# sequint.net
KiCad netlist of a schematic drawn in EAGLE
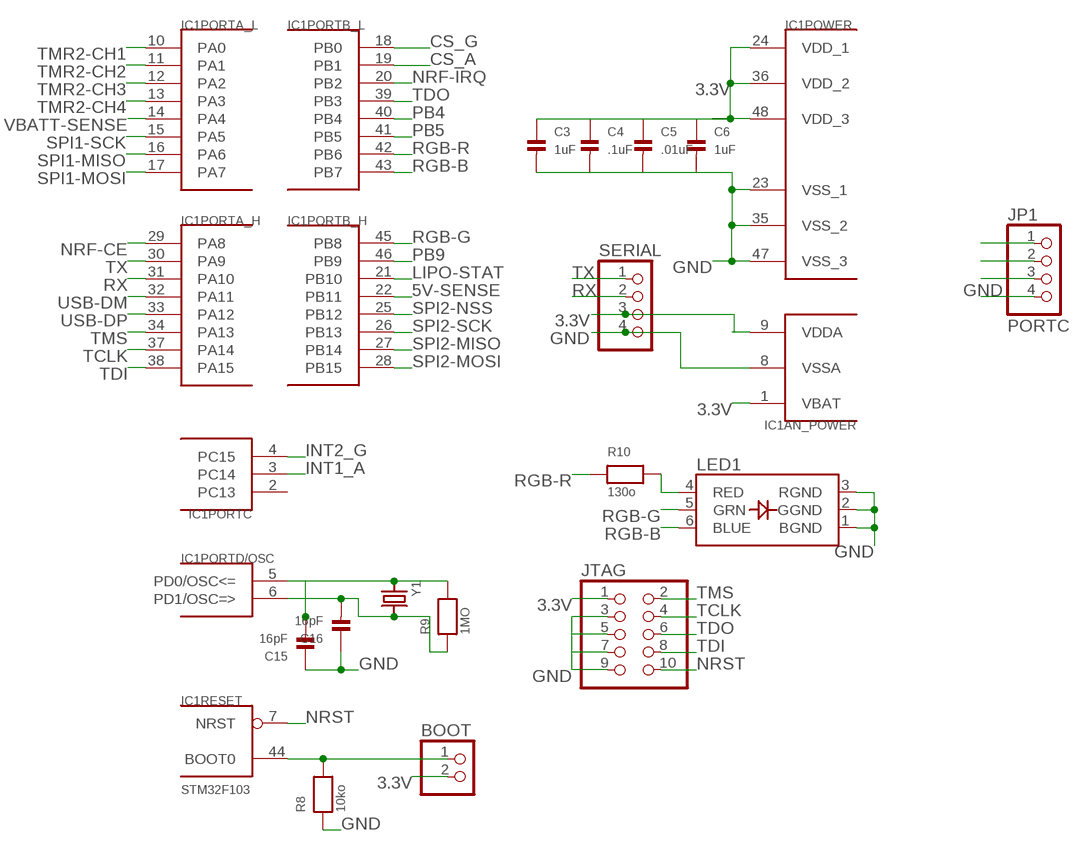
[diagram p0: schematic, sheet 1]
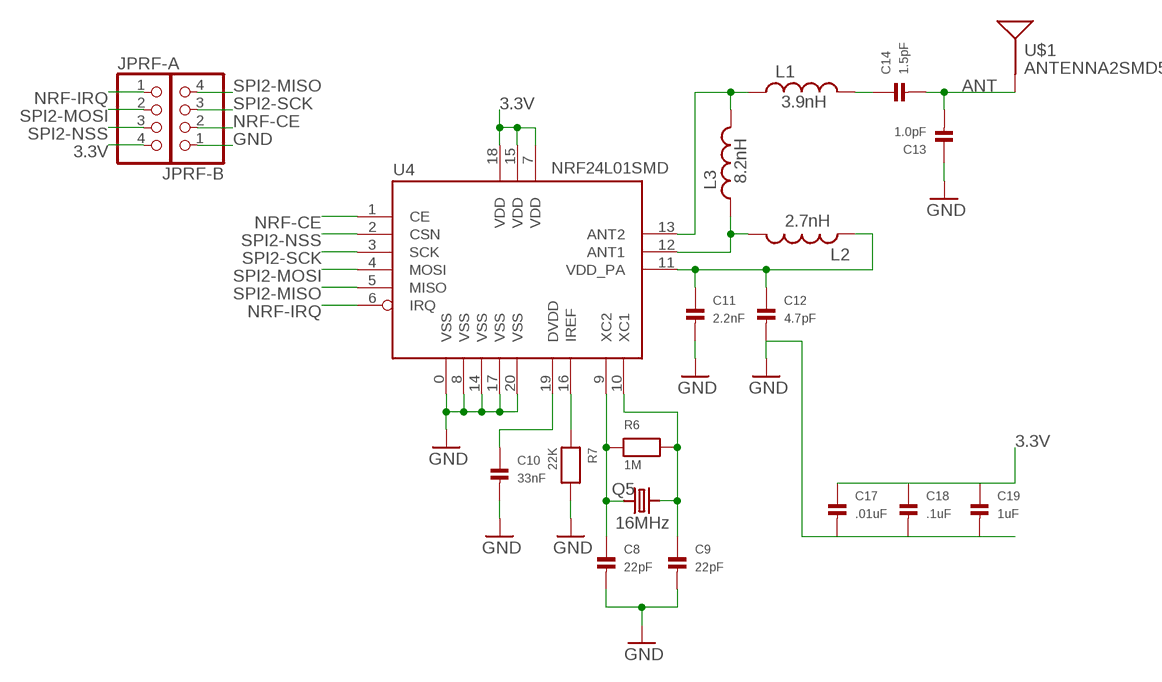
[diagram p1: schematic, sheet 2]
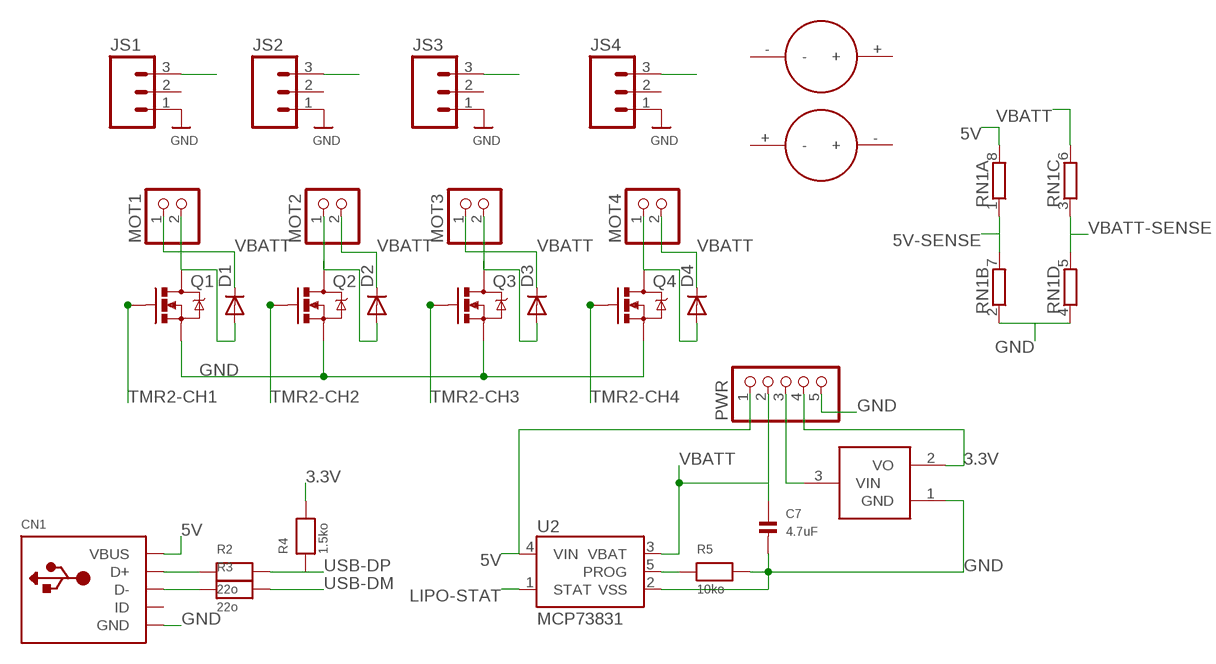
[diagram p2: schematic, sheet 3]
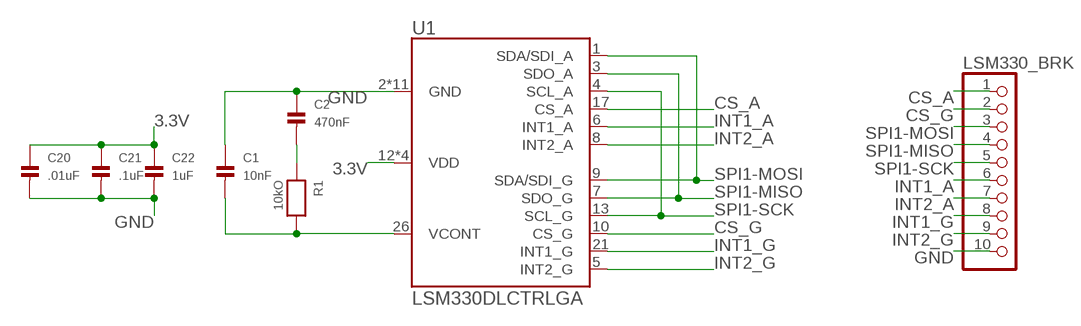
[diagram p3: schematic, sheet 4]

(export (version "E")
  (design (tool "Eeschema 10.0.6"))
  (components
    (comp (ref "C1")
      (value "10nF")
      (footprint "eagle-import:0402")
      (libsource (lib "eagle-import") (part "CAP_CERAMIC0402"))
    )
    (comp (ref "C2")
      (value "470nF")
      (footprint "eagle-import:0402")
      (libsource (lib "eagle-import") (part "CAP_CERAMIC0402"))
    )
    (comp (ref "C20")
      (value ".01uF")
      (footprint "eagle-import:0402")
      (libsource (lib "eagle-import") (part "CAP_CERAMIC0402"))
    )
    (comp (ref "C21")
      (value ".1uF")
      (footprint "eagle-import:0402")
      (libsource (lib "eagle-import") (part "CAP_CERAMIC0402"))
    )
    (comp (ref "C22")
      (value "1uF")
      (footprint "eagle-import:0402")
      (libsource (lib "eagle-import") (part "CAP_CERAMIC0402"))
    )
    (comp (ref "LSM330_BRK")
      (value "HEADER-1X10ROUND")
      (footprint "eagle-import:1X10_ROUND")
      (libsource (lib "eagle-import") (part "HEADER-1X10ROUND"))
    )
    (comp (ref "R1")
      (value "10kO")
      (footprint "eagle-import:0402")
      (libsource (lib "eagle-import") (part "RESISTOR0402"))
    )
    (comp (ref "U1")
      (value "LSM330DLCTRLGA")
      (footprint "eagle-import:LGA28L")
      (libsource (lib "eagle-import") (part "LSM330DLCTRLGA"))
    )
    (comp (ref "BOOT")
      (value "HEADER-1X2ROUND")
      (footprint "eagle-import:1X02_ROUND")
      (libsource (lib "eagle-import") (part "HEADER-1X2ROUND"))
    )
    (comp (ref "C3")
      (value "1uF")
      (footprint "eagle-import:0402")
      (libsource (lib "eagle-import") (part "CAP_CERAMIC0402"))
    )
    (comp (ref "C4")
      (value ".1uF")
      (footprint "eagle-import:0402")
      (libsource (lib "eagle-import") (part "CAP_CERAMIC0402"))
    )
    (comp (ref "C5")
      (value ".01uF")
      (footprint "eagle-import:0402")
      (libsource (lib "eagle-import") (part "CAP_CERAMIC0402"))
    )
    (comp (ref "C6")
      (value "1uF")
      (footprint "eagle-import:0402")
      (libsource (lib "eagle-import") (part "CAP_CERAMIC0402"))
    )
    (comp (ref "C15")
      (value "16pF")
      (footprint "eagle-import:0402")
      (libsource (lib "eagle-import") (part "CAP_CERAMIC0402"))
    )
    (comp (ref "C16")
      (value "16pF")
      (footprint "eagle-import:0402")
      (libsource (lib "eagle-import") (part "CAP_CERAMIC0402"))
    )
    (comp (ref "IC1")
      (value "STM32F103")
      (footprint "eagle-import:TQFP48")
      (libsource (lib "eagle-import") (part "STM32F10XCXT6"))
    )
    (comp (ref "JP1")
      (value "PORTC")
      (footprint "eagle-import:1X04_ROUND")
      (libsource (lib "eagle-import") (part "HEADER-1X4ROUND"))
    )
    (comp (ref "JTAG")
      (value "HEADER-2X5")
      (footprint "eagle-import:2X05")
      (libsource (lib "eagle-import") (part "HEADER-2X5"))
    )
    (comp (ref "LED1")
      (value "LED_RGB_PLCC6CREE-CLV6A")
      (footprint "eagle-import:RGBLED_PLCC6")
      (libsource (lib "eagle-import") (part "LED_RGB_PLCC6CREE-CLV6A"))
    )
    (comp (ref "R8")
      (value "10ko")
      (footprint "eagle-import:0402")
      (libsource (lib "eagle-import") (part "RESISTOR0402"))
    )
    (comp (ref "R9")
      (value "1MO")
      (footprint "eagle-import:0402")
      (libsource (lib "eagle-import") (part "RESISTOR0402"))
    )
    (comp (ref "R10")
      (value "130o")
      (footprint "eagle-import:0402")
      (libsource (lib "eagle-import") (part "RESISTOR0402"))
    )
    (comp (ref "SERIAL")
      (value "HEADER-1X4ROUND")
      (footprint "eagle-import:1X04_ROUND")
      (libsource (lib "eagle-import") (part "HEADER-1X4ROUND"))
    )
    (comp (ref "Y1")
      (value "CRYSTALSMD")
      (footprint "eagle-import:HC49UP")
      (libsource (lib "eagle-import") (part "CRYSTALSMD"))
    )
    (comp (ref "3.3VREG")
      (value "VREG")
      (footprint "eagle-import:SOT23-3")
      (libsource (lib "eagle-import") (part "VREG"))
    )
    (comp (ref "C7")
      (value "4.7uF")
      (footprint "eagle-import:0603")
      (libsource (lib "eagle-import") (part "CAP_CERAMIC0603"))
    )
    (comp (ref "CN1")
      (value "USBMINIB")
      (footprint "eagle-import:USB-MINIB")
      (libsource (lib "eagle-import") (part "USBMINIB"))
    )
    (comp (ref "D1")
      (value "DIODESOD523")
      (footprint "eagle-import:SOD523")
      (libsource (lib "eagle-import") (part "DIODESOD523"))
    )
    (comp (ref "D2")
      (value "DIODESOD523")
      (footprint "eagle-import:SOD523")
      (libsource (lib "eagle-import") (part "DIODESOD523"))
    )
    (comp (ref "D3")
      (value "DIODESOD523")
      (footprint "eagle-import:SOD523")
      (libsource (lib "eagle-import") (part "DIODESOD523"))
    )
    (comp (ref "D4")
      (value "DIODESOD523")
      (footprint "eagle-import:SOD523")
      (libsource (lib "eagle-import") (part "DIODESOD523"))
    )
    (comp (ref "JS1")
      (value "M03LOCK")
      (footprint "eagle-import:1X03_LOCK")
      (libsource (lib "eagle-import") (part "M03LOCK"))
    )
    (comp (ref "JS2")
      (value "M03LOCK")
      (footprint "eagle-import:1X03_LOCK")
      (libsource (lib "eagle-import") (part "M03LOCK"))
    )
    (comp (ref "JS3")
      (value "M03LOCK")
      (footprint "eagle-import:1X03_LOCK")
      (libsource (lib "eagle-import") (part "M03LOCK"))
    )
    (comp (ref "JS4")
      (value "M03LOCK")
      (footprint "eagle-import:1X03_LOCK")
      (libsource (lib "eagle-import") (part "M03LOCK"))
    )
    (comp (ref "MOT1")
      (value "HEADER-1X2ROUND")
      (footprint "eagle-import:1X02_ROUND")
      (libsource (lib "eagle-import") (part "HEADER-1X2ROUND"))
    )
    (comp (ref "MOT2")
      (value "HEADER-1X2ROUND")
      (footprint "eagle-import:1X02_ROUND")
      (libsource (lib "eagle-import") (part "HEADER-1X2ROUND"))
    )
    (comp (ref "MOT3")
      (value "HEADER-1X2ROUND")
      (footprint "eagle-import:1X02_ROUND")
      (libsource (lib "eagle-import") (part "HEADER-1X2ROUND"))
    )
    (comp (ref "MOT4")
      (value "HEADER-1X2ROUND")
      (footprint "eagle-import:1X02_ROUND")
      (libsource (lib "eagle-import") (part "HEADER-1X2ROUND"))
    )
    (comp (ref "PWR")
      (value "HEADER-1X5ROUND")
      (footprint "eagle-import:1X05_ROUND")
      (libsource (lib "eagle-import") (part "HEADER-1X5ROUND"))
    )
    (comp (ref "Q1")
      (value "MOSFET-N")
      (footprint "eagle-import:SOT23-3")
      (libsource (lib "eagle-import") (part "MOSFET-NCHANNELSMD"))
    )
    (comp (ref "Q2")
      (value "MOSFET-N")
      (footprint "eagle-import:SOT23-3")
      (libsource (lib "eagle-import") (part "MOSFET-NCHANNELSMD"))
    )
    (comp (ref "Q3")
      (value "MOSFET-N")
      (footprint "eagle-import:SOT23-3")
      (libsource (lib "eagle-import") (part "MOSFET-NCHANNELSMD"))
    )
    (comp (ref "Q4")
      (value "MOSFET-N")
      (footprint "eagle-import:SOT23-3")
      (libsource (lib "eagle-import") (part "MOSFET-NCHANNELSMD"))
    )
    (comp (ref "R2")
      (value "22o")
      (footprint "eagle-import:0402")
      (libsource (lib "eagle-import") (part "RESISTOR0402"))
    )
    (comp (ref "R3")
      (value "22o")
      (footprint "eagle-import:0402")
      (libsource (lib "eagle-import") (part "RESISTOR0402"))
    )
    (comp (ref "R4")
      (value "1.5ko")
      (footprint "eagle-import:0402")
      (libsource (lib "eagle-import") (part "RESISTOR0402"))
    )
    (comp (ref "R5")
      (value "10ko")
      (footprint "eagle-import:0402")
      (libsource (lib "eagle-import") (part "RESISTOR0402"))
    )
    (comp (ref "RN1")
      (value "RNETWORK")
      (footprint "eagle-import:RN8P-4R-CRA06S")
      (libsource (lib "eagle-import") (part "RNETWORK"))
    )
    (comp (ref "U$6")
      (value "MOT_RICCW")
      (footprint "eagle-import:MOT_RIC_BM_CW")
      (libsource (lib "eagle-import") (part "MOT_RICCW"))
    )
    (comp (ref "U$7")
      (value "MOT_RICCCW")
      (footprint "eagle-import:MOT_RIC_BM_CCW")
      (libsource (lib "eagle-import") (part "MOT_RICCCW"))
    )
    (comp (ref "U2")
      (value "MCP73831")
      (footprint "eagle-import:SOT23-5")
      (libsource (lib "eagle-import") (part "MCP73831"))
    )
    (comp (ref "C8")
      (value "22pF")
      (footprint "eagle-import:0402")
      (libsource (lib "eagle-import") (part "CAP_CERAMIC0402"))
    )
    (comp (ref "C9")
      (value "22pF")
      (footprint "eagle-import:0402")
      (libsource (lib "eagle-import") (part "CAP_CERAMIC0402"))
    )
    (comp (ref "C10")
      (value "33nF")
      (footprint "eagle-import:0402")
      (libsource (lib "eagle-import") (part "CAP_CERAMIC0402"))
    )
    (comp (ref "C11")
      (value "2.2nF")
      (footprint "eagle-import:0402")
      (libsource (lib "eagle-import") (part "CAP_CERAMIC0402"))
    )
    (comp (ref "C12")
      (value "4.7pF")
      (footprint "eagle-import:0402")
      (libsource (lib "eagle-import") (part "CAP_CERAMIC0402"))
    )
    (comp (ref "C13")
      (value "1.0pF")
      (footprint "eagle-import:0402")
      (libsource (lib "eagle-import") (part "CAP_CERAMIC0402"))
    )
    (comp (ref "C14")
      (value "1.5pF")
      (footprint "eagle-import:0402")
      (libsource (lib "eagle-import") (part "CAP_CERAMIC0402"))
    )
    (comp (ref "C17")
      (value ".01uF")
      (footprint "eagle-import:0402")
      (libsource (lib "eagle-import") (part "CAP_CERAMIC0402"))
    )
    (comp (ref "C18")
      (value ".1uF")
      (footprint "eagle-import:0402")
      (libsource (lib "eagle-import") (part "CAP_CERAMIC0402"))
    )
    (comp (ref "C19")
      (value "1uF")
      (footprint "eagle-import:0402")
      (libsource (lib "eagle-import") (part "CAP_CERAMIC0402"))
    )
    (comp (ref "JPRF-A")
      (value "HEADER-1X4ROUND")
      (footprint "eagle-import:1X04_ROUND")
      (libsource (lib "eagle-import") (part "HEADER-1X4ROUND"))
    )
    (comp (ref "JPRF-B")
      (value "HEADER-1X4ROUND")
      (footprint "eagle-import:1X04_ROUND")
      (libsource (lib "eagle-import") (part "HEADER-1X4ROUND"))
    )
    (comp (ref "L1")
      (value "3.9nH")
      (footprint "eagle-import:C0402")
      (libsource (lib "eagle-import") (part "INDUCTOR0402"))
    )
    (comp (ref "L2")
      (value "2.7nH")
      (footprint "eagle-import:C0402")
      (libsource (lib "eagle-import") (part "INDUCTOR0402"))
    )
    (comp (ref "L3")
      (value "8.2nH")
      (footprint "eagle-import:C0402")
      (libsource (lib "eagle-import") (part "INDUCTOR0402"))
    )
    (comp (ref "Q5")
      (value "16MHz")
      (footprint "eagle-import:HC49UP")
      (libsource (lib "eagle-import") (part "CRYSTALSMD"))
    )
    (comp (ref "R6")
      (value "1M")
      (footprint "eagle-import:0402")
      (libsource (lib "eagle-import") (part "RESISTOR0402"))
    )
    (comp (ref "R7")
      (value "22K")
      (footprint "eagle-import:0402")
      (libsource (lib "eagle-import") (part "RESISTOR0402"))
    )
    (comp (ref "U$1")
      (value "ANTENNA2SMD5")
      (footprint "eagle-import:ANTENNA-CHIP5")
      (libsource (lib "eagle-import") (part "ANTENNA2SMD5"))
    )
    (comp (ref "U4")
      (value "NRF24L01SMD")
      (footprint "eagle-import:QFN20")
      (libsource (lib "eagle-import") (part "NRF24L01SMD"))
    )
  )
  (nets
    (net (code "1") (name "3.3V") (class "Default")
      (node (ref "3.3VREG") (pin "2") (pinfunction "VO_2") (pintype "bidirectional"))
      (node (ref "BOOT") (pin "2") (pinfunction "2_2") (pintype "passive"))
      (node (ref "C17") (pin "1") (pinfunction "P$1_1") (pintype "passive"))
      (node (ref "C18") (pin "1") (pinfunction "P$1_1") (pintype "passive"))
      (node (ref "C19") (pin "1") (pinfunction "P$1_1") (pintype "passive"))
      (node (ref "C20") (pin "1") (pinfunction "P$1_1") (pintype "passive"))
      (node (ref "C21") (pin "1") (pinfunction "P$1_1") (pintype "passive"))
      (node (ref "C22") (pin "1") (pinfunction "P$1_1") (pintype "passive"))
      (node (ref "C3") (pin "1") (pinfunction "P$1_1") (pintype "passive"))
      (node (ref "C4") (pin "1") (pinfunction "P$1_1") (pintype "passive"))
      (node (ref "C5") (pin "1") (pinfunction "P$1_1") (pintype "passive"))
      (node (ref "C6") (pin "1") (pinfunction "P$1_1") (pintype "passive"))
      (node (ref "IC1") (pin "1") (pinfunction "VBAT_1") (pintype "power_in"))
      (node (ref "IC1") (pin "24") (pinfunction "VDD_1_24") (pintype "power_in"))
      (node (ref "IC1") (pin "36") (pinfunction "VDD_2_36") (pintype "power_in"))
      (node (ref "IC1") (pin "48") (pinfunction "VDD_3_48") (pintype "power_in"))
      (node (ref "IC1") (pin "9") (pinfunction "VDDA_9") (pintype "power_in"))
      (node (ref "JPRF-A") (pin "4") (pinfunction "4_4") (pintype "passive"))
      (node (ref "JTAG") (pin "1") (pinfunction "1_1") (pintype "passive"))
      (node (ref "PWR") (pin "4") (pinfunction "4_4") (pintype "passive"))
      (node (ref "R4") (pin "2") (pinfunction "2_2") (pintype "passive"))
      (node (ref "SERIAL") (pin "3") (pinfunction "3_3") (pintype "passive"))
      (node (ref "U1") (pin "12") (pinfunction "VDD_12") (pintype "bidirectional"))
      (node (ref "U1") (pin "15") (pinfunction "VDD_15") (pintype "bidirectional"))
      (node (ref "U1") (pin "22") (pinfunction "VDD_22") (pintype "bidirectional"))
      (node (ref "U1") (pin "28") (pinfunction "VDD_28") (pintype "bidirectional"))
      (node (ref "U4") (pin "15") (pinfunction "VDD_15") (pintype "power_in"))
      (node (ref "U4") (pin "18") (pinfunction "VDD_18") (pintype "power_in"))
      (node (ref "U4") (pin "7") (pinfunction "VDD_7") (pintype "power_in"))
    )
    (net (code "2") (name "5V") (class "Default")
      (node (ref "CN1") (pin "VBUS") (pinfunction "VBUS_VBUS") (pintype "power_in"))
      (node (ref "PWR") (pin "1") (pinfunction "1_1") (pintype "passive"))
      (node (ref "RN1") (pin "8") (pinfunction "2_8") (pintype "passive"))
      (node (ref "U2") (pin "4") (pinfunction "VIN_4") (pintype "power_in"))
    )
    (net (code "3") (name "5V-SENSE") (class "Default")
      (node (ref "IC1") (pin "22") (pinfunction "PB11_22") (pintype "bidirectional"))
      (node (ref "RN1") (pin "1") (pinfunction "1_1") (pintype "passive"))
      (node (ref "RN1") (pin "7") (pinfunction "2_7") (pintype "passive"))
    )
    (net (code "4") (name "ANT") (class "Default")
      (node (ref "C13") (pin "2") (pinfunction "P$2_2") (pintype "passive"))
      (node (ref "C14") (pin "2") (pinfunction "P$2_2") (pintype "passive"))
      (node (ref "U$1") (pin "FEED") (pinfunction "SIGNAL_FEED") (pintype "bidirectional"))
    )
    (net (code "5") (name "CS_A") (class "Default")
      (node (ref "IC1") (pin "19") (pinfunction "PB1_19") (pintype "bidirectional"))
      (node (ref "LSM330_BRK") (pin "1") (pinfunction "1_1") (pintype "passive"))
      (node (ref "U1") (pin "17") (pinfunction "CS_A_17") (pintype "bidirectional"))
    )
    (net (code "6") (name "CS_G") (class "Default")
      (node (ref "IC1") (pin "18") (pinfunction "PB0_18") (pintype "bidirectional"))
      (node (ref "LSM330_BRK") (pin "2") (pinfunction "2_2") (pintype "passive"))
      (node (ref "U1") (pin "10") (pinfunction "CS_G_10") (pintype "bidirectional"))
    )
    (net (code "7") (name "GND") (class "Default")
      (node (ref "3.3VREG") (pin "1") (pinfunction "GND_1") (pintype "bidirectional"))
      (node (ref "C1") (pin "1") (pinfunction "P$1_1") (pintype "passive"))
      (node (ref "C10") (pin "2") (pinfunction "P$2_2") (pintype "passive"))
      (node (ref "C11") (pin "2") (pinfunction "P$2_2") (pintype "passive"))
      (node (ref "C12") (pin "2") (pinfunction "P$2_2") (pintype "passive"))
      (node (ref "C13") (pin "1") (pinfunction "P$1_1") (pintype "passive"))
      (node (ref "C15") (pin "1") (pinfunction "P$1_1") (pintype "passive"))
      (node (ref "C16") (pin "1") (pinfunction "P$1_1") (pintype "passive"))
      (node (ref "C17") (pin "2") (pinfunction "P$2_2") (pintype "passive"))
      (node (ref "C18") (pin "2") (pinfunction "P$2_2") (pintype "passive"))
      (node (ref "C19") (pin "2") (pinfunction "P$2_2") (pintype "passive"))
      (node (ref "C2") (pin "1") (pinfunction "P$1_1") (pintype "passive"))
      (node (ref "C20") (pin "2") (pinfunction "P$2_2") (pintype "passive"))
      (node (ref "C21") (pin "2") (pinfunction "P$2_2") (pintype "passive"))
      (node (ref "C22") (pin "2") (pinfunction "P$2_2") (pintype "passive"))
      (node (ref "C3") (pin "2") (pinfunction "P$2_2") (pintype "passive"))
      (node (ref "C4") (pin "2") (pinfunction "P$2_2") (pintype "passive"))
      (node (ref "C5") (pin "2") (pinfunction "P$2_2") (pintype "passive"))
      (node (ref "C6") (pin "2") (pinfunction "P$2_2") (pintype "passive"))
      (node (ref "C7") (pin "2") (pinfunction "P$2_2") (pintype "passive"))
      (node (ref "C8") (pin "2") (pinfunction "P$2_2") (pintype "passive"))
      (node (ref "C9") (pin "2") (pinfunction "P$2_2") (pintype "passive"))
      (node (ref "CN1") (pin "GND") (pinfunction "GND_GND") (pintype "power_in"))
      (node (ref "IC1") (pin "23") (pinfunction "VSS_1_23") (pintype "power_in"))
      (node (ref "IC1") (pin "35") (pinfunction "VSS_2_35") (pintype "power_in"))
      (node (ref "IC1") (pin "47") (pinfunction "VSS_3_47") (pintype "power_in"))
      (node (ref "IC1") (pin "8") (pinfunction "VSSA_8") (pintype "power_in"))
      (node (ref "JP1") (pin "4") (pinfunction "4_4") (pintype "passive"))
      (node (ref "JPRF-B") (pin "1") (pinfunction "1_1") (pintype "passive"))
      (node (ref "JS1") (pin "1") (pinfunction "1_1") (pintype "passive"))
      (node (ref "JS2") (pin "1") (pinfunction "1_1") (pintype "passive"))
      (node (ref "JS3") (pin "1") (pinfunction "1_1") (pintype "passive"))
      (node (ref "JS4") (pin "1") (pinfunction "1_1") (pintype "passive"))
      (node (ref "JTAG") (pin "3") (pinfunction "3_3") (pintype "passive"))
      (node (ref "JTAG") (pin "5") (pinfunction "5_5") (pintype "passive"))
      (node (ref "JTAG") (pin "7") (pinfunction "7_7") (pintype "passive"))
      (node (ref "JTAG") (pin "9") (pinfunction "9_9") (pintype "passive"))
      (node (ref "LED1") (pin "1") (pinfunction "BGND_1") (pintype "power_in"))
      (node (ref "LED1") (pin "2") (pinfunction "GGND_2") (pintype "power_in"))
      (node (ref "LED1") (pin "3") (pinfunction "RGND_3") (pintype "power_in"))
      (node (ref "LSM330_BRK") (pin "10") (pinfunction "10_10") (pintype "passive"))
      (node (ref "PWR") (pin "5") (pinfunction "5_5") (pintype "passive"))
      (node (ref "Q1") (pin "2") (pinfunction "S_2") (pintype "passive"))
      (node (ref "Q2") (pin "2") (pinfunction "S_2") (pintype "passive"))
      (node (ref "Q3") (pin "2") (pinfunction "S_2") (pintype "passive"))
      (node (ref "Q4") (pin "2") (pinfunction "S_2") (pintype "passive"))
      (node (ref "R5") (pin "2") (pinfunction "2_2") (pintype "passive"))
      (node (ref "R7") (pin "2") (pinfunction "2_2") (pintype "passive"))
      (node (ref "R8") (pin "1") (pinfunction "1_1") (pintype "passive"))
      (node (ref "RN1") (pin "2") (pinfunction "1_2") (pintype "passive"))
      (node (ref "RN1") (pin "4") (pinfunction "1_4") (pintype "passive"))
      (node (ref "SERIAL") (pin "4") (pinfunction "4_4") (pintype "passive"))
      (node (ref "U1") (pin "11") (pinfunction "GND_11") (pintype "bidirectional"))
      (node (ref "U1") (pin "14") (pinfunction "GND_14") (pintype "bidirectional"))
      (node (ref "U1") (pin "16") (pinfunction "GND_16") (pintype "bidirectional"))
      (node (ref "U1") (pin "18") (pinfunction "GND_18") (pintype "bidirectional"))
      (node (ref "U1") (pin "19") (pinfunction "GND_19") (pintype "bidirectional"))
      (node (ref "U1") (pin "2") (pinfunction "GND_2") (pintype "bidirectional"))
      (node (ref "U1") (pin "20") (pinfunction "GND_20") (pintype "bidirectional"))
      (node (ref "U1") (pin "23") (pinfunction "GND_23") (pintype "bidirectional"))
      (node (ref "U1") (pin "24") (pinfunction "GND_24") (pintype "bidirectional"))
      (node (ref "U1") (pin "25") (pinfunction "GND_25") (pintype "bidirectional"))
      (node (ref "U1") (pin "27") (pinfunction "GND_27") (pintype "bidirectional"))
      (node (ref "U2") (pin "2") (pinfunction "VSS_2") (pintype "power_in"))
      (node (ref "U4") (pin "0") (pinfunction "VSS_0") (pintype "power_in"))
      (node (ref "U4") (pin "14") (pinfunction "VSS_14") (pintype "power_in"))
      (node (ref "U4") (pin "17") (pinfunction "VSS_17") (pintype "power_in"))
      (node (ref "U4") (pin "20") (pinfunction "VSS_20") (pintype "power_in"))
      (node (ref "U4") (pin "8") (pinfunction "VSS_8") (pintype "power_in"))
    )
    (net (code "8") (name "INT1_A") (class "Default")
      (node (ref "IC1") (pin "3") (pinfunction "PC14_3") (pintype "bidirectional"))
      (node (ref "LSM330_BRK") (pin "6") (pinfunction "6_6") (pintype "passive"))
      (node (ref "U1") (pin "6") (pinfunction "INT1_A_6") (pintype "bidirectional"))
    )
    (net (code "9") (name "INT1_G") (class "Default")
      (node (ref "LSM330_BRK") (pin "8") (pinfunction "8_8") (pintype "passive"))
      (node (ref "U1") (pin "21") (pinfunction "INT1_G_21") (pintype "bidirectional"))
    )
    (net (code "10") (name "INT2_A") (class "Default")
      (node (ref "LSM330_BRK") (pin "7") (pinfunction "7_7") (pintype "passive"))
      (node (ref "U1") (pin "8") (pinfunction "INT2_A_8") (pintype "bidirectional"))
    )
    (net (code "11") (name "INT2_G") (class "Default")
      (node (ref "IC1") (pin "4") (pinfunction "PC15_4") (pintype "bidirectional"))
      (node (ref "LSM330_BRK") (pin "9") (pinfunction "9_9") (pintype "passive"))
      (node (ref "U1") (pin "5") (pinfunction "INT2_G_5") (pintype "bidirectional"))
    )
    (net (code "12") (name "LIPO-STAT") (class "Default")
      (node (ref "IC1") (pin "21") (pinfunction "PB10_21") (pintype "bidirectional"))
      (node (ref "U2") (pin "1") (pinfunction "STAT_1") (pintype "output"))
    )
    (net (code "13") (name "NRF-CE") (class "Default")
      (node (ref "IC1") (pin "29") (pinfunction "PA8_29") (pintype "bidirectional"))
      (node (ref "JPRF-B") (pin "2") (pinfunction "2_2") (pintype "passive"))
      (node (ref "U4") (pin "1") (pinfunction "CE_1") (pintype "input"))
    )
    (net (code "14") (name "NRF-IRQ") (class "Default")
      (node (ref "IC1") (pin "20") (pinfunction "PB2_20") (pintype "bidirectional"))
      (node (ref "JPRF-A") (pin "1") (pinfunction "1_1") (pintype "passive"))
      (node (ref "U4") (pin "6") (pinfunction "IRQ_6") (pintype "output"))
    )
    (net (code "15") (name "NRST") (class "Default")
      (node (ref "IC1") (pin "7") (pinfunction "NRST_7") (pintype "input"))
      (node (ref "JTAG") (pin "10") (pinfunction "10_10") (pintype "passive"))
    )
    (net (code "16") (name "Net-(3.3VREG-VIN)") (class "Default")
      (node (ref "3.3VREG") (pin "3") (pinfunction "VIN_3") (pintype "bidirectional"))
      (node (ref "PWR") (pin "3") (pinfunction "3_3") (pintype "passive"))
    )
    (net (code "17") (name "Net-(C1-P$2)") (class "Default")
      (node (ref "C1") (pin "2") (pinfunction "P$2_2") (pintype "passive"))
      (node (ref "R1") (pin "2") (pinfunction "2_2") (pintype "passive"))
      (node (ref "U1") (pin "26") (pinfunction "VCONT_26") (pintype "bidirectional"))
    )
    (net (code "18") (name "Net-(C2-P$2)") (class "Default")
      (node (ref "C2") (pin "2") (pinfunction "P$2_2") (pintype "passive"))
      (node (ref "R1") (pin "1") (pinfunction "1_1") (pintype "passive"))
    )
    (net (code "19") (name "Net-(C8-P$1)") (class "Default")
      (node (ref "C8") (pin "1") (pinfunction "P$1_1") (pintype "passive"))
      (node (ref "Q5") (pin "1") (pinfunction "1_1") (pintype "passive"))
      (node (ref "R6") (pin "1") (pinfunction "1_1") (pintype "passive"))
      (node (ref "U4") (pin "9") (pinfunction "XC2_9") (pintype "input"))
    )
    (net (code "20") (name "Net-(C9-P$1)") (class "Default")
      (node (ref "C9") (pin "1") (pinfunction "P$1_1") (pintype "passive"))
      (node (ref "Q5") (pin "2") (pinfunction "2_2") (pintype "passive"))
      (node (ref "R6") (pin "2") (pinfunction "2_2") (pintype "passive"))
      (node (ref "U4") (pin "10") (pinfunction "XC1_10") (pintype "input"))
    )
    (net (code "21") (name "Net-(C10-P$1)") (class "Default")
      (node (ref "C10") (pin "1") (pinfunction "P$1_1") (pintype "passive"))
      (node (ref "U4") (pin "19") (pinfunction "DVDD_19") (pintype "power_in"))
    )
    (net (code "22") (name "Net-(C11-P$1)") (class "Default")
      (node (ref "C11") (pin "1") (pinfunction "P$1_1") (pintype "passive"))
      (node (ref "C12") (pin "1") (pinfunction "P$1_1") (pintype "passive"))
      (node (ref "L2") (pin "1") (pinfunction "1_1") (pintype "passive"))
      (node (ref "U4") (pin "11") (pinfunction "VDD_PA_11") (pintype "power_in"))
    )
    (net (code "23") (name "Net-(C14-P$1)") (class "Default")
      (node (ref "C14") (pin "1") (pinfunction "P$1_1") (pintype "passive"))
      (node (ref "L1") (pin "2") (pinfunction "2_2") (pintype "passive"))
    )
    (net (code "24") (name "Net-(C15-P$2)") (class "Default")
      (node (ref "C15") (pin "2") (pinfunction "P$2_2") (pintype "passive"))
      (node (ref "IC1") (pin "5") (pinfunction "PD0/OSC<=_5") (pintype "bidirectional"))
      (node (ref "R9") (pin "2") (pinfunction "2_2") (pintype "passive"))
      (node (ref "Y1") (pin "1") (pinfunction "1_1") (pintype "passive"))
    )
    (net (code "25") (name "Net-(C16-P$2)") (class "Default")
      (node (ref "C16") (pin "2") (pinfunction "P$2_2") (pintype "passive"))
      (node (ref "IC1") (pin "6") (pinfunction "PD1/OSC=>_6") (pintype "bidirectional"))
      (node (ref "R9") (pin "1") (pinfunction "1_1") (pintype "passive"))
      (node (ref "Y1") (pin "2") (pinfunction "2_2") (pintype "passive"))
    )
    (net (code "26") (name "Net-(CN1-PadD+)") (class "Default")
      (node (ref "CN1") (pin "D+") (pinfunction "D+_D+") (pintype "bidirectional"))
      (node (ref "R2") (pin "1") (pinfunction "1_1") (pintype "passive"))
    )
    (net (code "27") (name "Net-(CN1-PadD-)") (class "Default")
      (node (ref "CN1") (pin "D-") (pinfunction "D-_D-") (pintype "bidirectional"))
      (node (ref "R3") (pin "1") (pinfunction "1_1") (pintype "passive"))
    )
    (net (code "28") (name "Net-(IC1I-BOOT0)") (class "Default")
      (node (ref "BOOT") (pin "1") (pinfunction "1_1") (pintype "passive"))
      (node (ref "IC1") (pin "44") (pinfunction "BOOT0_44") (pintype "input"))
      (node (ref "R8") (pin "2") (pinfunction "2_2") (pintype "passive"))
    )
    (net (code "29") (name "Net-(LED1-RED)") (class "Default")
      (node (ref "LED1") (pin "4") (pinfunction "RED_4") (pintype "bidirectional"))
      (node (ref "R10") (pin "2") (pinfunction "2_2") (pintype "passive"))
    )
    (net (code "30") (name "Net-(Q1-D)") (class "Default")
      (node (ref "D1") (pin "A") (pinfunction "A_A") (pintype "passive"))
      (node (ref "MOT1") (pin "2") (pinfunction "2_2") (pintype "passive"))
      (node (ref "Q1") (pin "3") (pinfunction "D_3") (pintype "passive"))
    )
    (net (code "31") (name "Net-(Q2-D)") (class "Default")
      (node (ref "D2") (pin "A") (pinfunction "A_A") (pintype "passive"))
      (node (ref "MOT2") (pin "1") (pinfunction "1_1") (pintype "passive"))
      (node (ref "Q2") (pin "3") (pinfunction "D_3") (pintype "passive"))
    )
    (net (code "32") (name "Net-(Q3-D)") (class "Default")
      (node (ref "D3") (pin "A") (pinfunction "A_A") (pintype "passive"))
      (node (ref "MOT3") (pin "2") (pinfunction "2_2") (pintype "passive"))
      (node (ref "Q3") (pin "3") (pinfunction "D_3") (pintype "passive"))
    )
    (net (code "33") (name "Net-(Q4-D)") (class "Default")
      (node (ref "D4") (pin "A") (pinfunction "A_A") (pintype "passive"))
      (node (ref "MOT4") (pin "1") (pinfunction "1_1") (pintype "passive"))
      (node (ref "Q4") (pin "3") (pinfunction "D_3") (pintype "passive"))
    )
    (net (code "34") (name "Net-(U2-PROG)") (class "Default")
      (node (ref "R5") (pin "1") (pinfunction "1_1") (pintype "passive"))
      (node (ref "U2") (pin "5") (pinfunction "PROG_5") (pintype "input"))
    )
    (net (code "35") (name "Net-(U4-ANT1)") (class "Default")
      (node (ref "L2") (pin "2") (pinfunction "2_2") (pintype "passive"))
      (node (ref "L3") (pin "1") (pinfunction "1_1") (pintype "passive"))
      (node (ref "U4") (pin "12") (pinfunction "ANT1_12") (pintype "output"))
    )
    (net (code "36") (name "Net-(U4-ANT2)") (class "Default")
      (node (ref "L1") (pin "1") (pinfunction "1_1") (pintype "passive"))
      (node (ref "L3") (pin "2") (pinfunction "2_2") (pintype "passive"))
      (node (ref "U4") (pin "13") (pinfunction "ANT2_13") (pintype "output"))
    )
    (net (code "37") (name "Net-(U4-IREF)") (class "Default")
      (node (ref "R7") (pin "1") (pinfunction "1_1") (pintype "passive"))
      (node (ref "U4") (pin "16") (pinfunction "IREF_16") (pintype "input"))
    )
    (net (code "38") (name "PB4") (class "Default")
      (node (ref "IC1") (pin "40") (pinfunction "PB4_40") (pintype "bidirectional"))
      (node (ref "JP1") (pin "1") (pinfunction "1_1") (pintype "passive"))
    )
    (net (code "39") (name "PB5") (class "Default")
      (node (ref "IC1") (pin "41") (pinfunction "PB5_41") (pintype "bidirectional"))
      (node (ref "JP1") (pin "2") (pinfunction "2_2") (pintype "passive"))
    )
    (net (code "40") (name "PB9") (class "Default")
      (node (ref "IC1") (pin "46") (pinfunction "PB9_46") (pintype "bidirectional"))
      (node (ref "JP1") (pin "3") (pinfunction "3_3") (pintype "passive"))
    )
    (net (code "41") (name "RGB-B") (class "Default")
      (node (ref "IC1") (pin "43") (pinfunction "PB7_43") (pintype "bidirectional"))
      (node (ref "LED1") (pin "6") (pinfunction "BLUE_6") (pintype "bidirectional"))
    )
    (net (code "42") (name "RGB-G") (class "Default")
      (node (ref "IC1") (pin "45") (pinfunction "PB8_45") (pintype "bidirectional"))
      (node (ref "LED1") (pin "5") (pinfunction "GRN_5") (pintype "bidirectional"))
    )
    (net (code "43") (name "RGB-R") (class "Default")
      (node (ref "IC1") (pin "42") (pinfunction "PB6_42") (pintype "bidirectional"))
      (node (ref "R10") (pin "1") (pinfunction "1_1") (pintype "passive"))
    )
    (net (code "44") (name "RX") (class "Default")
      (node (ref "IC1") (pin "31") (pinfunction "PA10_31") (pintype "bidirectional"))
      (node (ref "SERIAL") (pin "2") (pinfunction "2_2") (pintype "passive"))
    )
    (net (code "45") (name "SPI1-MISO") (class "Default")
      (node (ref "IC1") (pin "16") (pinfunction "PA6_16") (pintype "bidirectional"))
      (node (ref "LSM330_BRK") (pin "4") (pinfunction "4_4") (pintype "passive"))
      (node (ref "U1") (pin "3") (pinfunction "SDO_A_3") (pintype "bidirectional"))
      (node (ref "U1") (pin "7") (pinfunction "SDO_G_7") (pintype "bidirectional"))
    )
    (net (code "46") (name "SPI1-MOSI") (class "Default")
      (node (ref "IC1") (pin "17") (pinfunction "PA7_17") (pintype "bidirectional"))
      (node (ref "LSM330_BRK") (pin "3") (pinfunction "3_3") (pintype "passive"))
      (node (ref "U1") (pin "1") (pinfunction "SDA/SDI_A_1") (pintype "bidirectional"))
      (node (ref "U1") (pin "9") (pinfunction "SDA/SDI_G_9") (pintype "bidirectional"))
    )
    (net (code "47") (name "SPI1-SCK") (class "Default")
      (node (ref "IC1") (pin "15") (pinfunction "PA5_15") (pintype "bidirectional"))
      (node (ref "LSM330_BRK") (pin "5") (pinfunction "5_5") (pintype "passive"))
      (node (ref "U1") (pin "13") (pinfunction "SCL_G_13") (pintype "bidirectional"))
      (node (ref "U1") (pin "4") (pinfunction "SCL_A_4") (pintype "bidirectional"))
    )
    (net (code "48") (name "SPI2-MISO") (class "Default")
      (node (ref "IC1") (pin "27") (pinfunction "PB14_27") (pintype "bidirectional"))
      (node (ref "JPRF-B") (pin "4") (pinfunction "4_4") (pintype "passive"))
      (node (ref "U4") (pin "5") (pinfunction "MISO_5") (pintype "output"))
    )
    (net (code "49") (name "SPI2-MOSI") (class "Default")
      (node (ref "IC1") (pin "28") (pinfunction "PB15_28") (pintype "bidirectional"))
      (node (ref "JPRF-A") (pin "2") (pinfunction "2_2") (pintype "passive"))
      (node (ref "U4") (pin "4") (pinfunction "MOSI_4") (pintype "input"))
    )
    (net (code "50") (name "SPI2-NSS") (class "Default")
      (node (ref "IC1") (pin "25") (pinfunction "PB12_25") (pintype "bidirectional"))
      (node (ref "JPRF-A") (pin "3") (pinfunction "3_3") (pintype "passive"))
      (node (ref "U4") (pin "2") (pinfunction "CSN_2") (pintype "input"))
    )
    (net (code "51") (name "SPI2-SCK") (class "Default")
      (node (ref "IC1") (pin "26") (pinfunction "PB13_26") (pintype "bidirectional"))
      (node (ref "JPRF-B") (pin "3") (pinfunction "3_3") (pintype "passive"))
      (node (ref "U4") (pin "3") (pinfunction "SCK_3") (pintype "input"))
    )
    (net (code "52") (name "TCLK") (class "Default")
      (node (ref "IC1") (pin "37") (pinfunction "PA14_37") (pintype "bidirectional"))
      (node (ref "JTAG") (pin "4") (pinfunction "4_4") (pintype "passive"))
    )
    (net (code "53") (name "TDI") (class "Default")
      (node (ref "IC1") (pin "38") (pinfunction "PA15_38") (pintype "bidirectional"))
      (node (ref "JTAG") (pin "8") (pinfunction "8_8") (pintype "passive"))
    )
    (net (code "54") (name "TDO") (class "Default")
      (node (ref "IC1") (pin "39") (pinfunction "PB3_39") (pintype "bidirectional"))
      (node (ref "JTAG") (pin "6") (pinfunction "6_6") (pintype "passive"))
    )
    (net (code "55") (name "TMR2-CH1") (class "Default")
      (node (ref "IC1") (pin "10") (pinfunction "PA0_10") (pintype "bidirectional"))
      (node (ref "JS1") (pin "3") (pinfunction "3_3") (pintype "passive"))
      (node (ref "Q1") (pin "1") (pinfunction "G_1") (pintype "passive"))
    )
    (net (code "56") (name "TMR2-CH2") (class "Default")
      (node (ref "IC1") (pin "11") (pinfunction "PA1_11") (pintype "bidirectional"))
      (node (ref "JS2") (pin "3") (pinfunction "3_3") (pintype "passive"))
      (node (ref "Q2") (pin "1") (pinfunction "G_1") (pintype "passive"))
    )
    (net (code "57") (name "TMR2-CH3") (class "Default")
      (node (ref "IC1") (pin "12") (pinfunction "PA2_12") (pintype "bidirectional"))
      (node (ref "JS3") (pin "3") (pinfunction "3_3") (pintype "passive"))
      (node (ref "Q3") (pin "1") (pinfunction "G_1") (pintype "passive"))
    )
    (net (code "58") (name "TMR2-CH4") (class "Default")
      (node (ref "IC1") (pin "13") (pinfunction "PA3_13") (pintype "bidirectional"))
      (node (ref "JS4") (pin "3") (pinfunction "3_3") (pintype "passive"))
      (node (ref "Q4") (pin "1") (pinfunction "G_1") (pintype "passive"))
    )
    (net (code "59") (name "TMS") (class "Default")
      (node (ref "IC1") (pin "34") (pinfunction "PA13_34") (pintype "bidirectional"))
      (node (ref "JTAG") (pin "2") (pinfunction "2_2") (pintype "passive"))
    )
    (net (code "60") (name "TX") (class "Default")
      (node (ref "IC1") (pin "30") (pinfunction "PA9_30") (pintype "bidirectional"))
      (node (ref "SERIAL") (pin "1") (pinfunction "1_1") (pintype "passive"))
    )
    (net (code "61") (name "USB-DM") (class "Default")
      (node (ref "IC1") (pin "32") (pinfunction "PA11_32") (pintype "bidirectional"))
      (node (ref "R3") (pin "2") (pinfunction "2_2") (pintype "passive"))
    )
    (net (code "62") (name "USB-DP") (class "Default")
      (node (ref "IC1") (pin "33") (pinfunction "PA12_33") (pintype "bidirectional"))
      (node (ref "R2") (pin "2") (pinfunction "2_2") (pintype "passive"))
      (node (ref "R4") (pin "1") (pinfunction "1_1") (pintype "passive"))
    )
    (net (code "63") (name "VBATT") (class "Default")
      (node (ref "C7") (pin "1") (pinfunction "P$1_1") (pintype "passive"))
      (node (ref "D1") (pin "C") (pinfunction "C_C") (pintype "passive"))
      (node (ref "D2") (pin "C") (pinfunction "C_C") (pintype "passive"))
      (node (ref "D3") (pin "C") (pinfunction "C_C") (pintype "passive"))
      (node (ref "D4") (pin "C") (pinfunction "C_C") (pintype "passive"))
      (node (ref "MOT1") (pin "1") (pinfunction "1_1") (pintype "passive"))
      (node (ref "MOT2") (pin "2") (pinfunction "2_2") (pintype "passive"))
      (node (ref "MOT3") (pin "1") (pinfunction "1_1") (pintype "passive"))
      (node (ref "MOT4") (pin "2") (pinfunction "2_2") (pintype "passive"))
      (node (ref "PWR") (pin "2") (pinfunction "2_2") (pintype "passive"))
      (node (ref "RN1") (pin "6") (pinfunction "2_6") (pintype "passive"))
      (node (ref "U2") (pin "3") (pinfunction "VBAT_3") (pintype "power_in"))
    )
    (net (code "64") (name "VBATT-SENSE") (class "Default")
      (node (ref "IC1") (pin "14") (pinfunction "PA4_14") (pintype "bidirectional"))
      (node (ref "RN1") (pin "3") (pinfunction "1_3") (pintype "passive"))
      (node (ref "RN1") (pin "5") (pinfunction "2_5") (pintype "passive"))
    )
    (net (code "65") (name "unconnected-(CN1-PadID)") (class "Default")
      (node (ref "CN1") (pin "ID") (pinfunction "ID_ID") (pintype "bidirectional"))
    )
    (net (code "66") (name "unconnected-(IC1F-PC13-Pad2)") (class "Default")
      (node (ref "IC1") (pin "2") (pinfunction "PC13_2") (pintype "bidirectional"))
    )
    (net (code "67") (name "unconnected-(JS1-Pad2)") (class "Default")
      (node (ref "JS1") (pin "2") (pinfunction "2_2") (pintype "passive"))
    )
    (net (code "68") (name "unconnected-(JS2-Pad2)") (class "Default")
      (node (ref "JS2") (pin "2") (pinfunction "2_2") (pintype "passive"))
    )
    (net (code "69") (name "unconnected-(JS3-Pad2)") (class "Default")
      (node (ref "JS3") (pin "2") (pinfunction "2_2") (pintype "passive"))
    )
    (net (code "70") (name "unconnected-(JS4-Pad2)") (class "Default")
      (node (ref "JS4") (pin "2") (pinfunction "2_2") (pintype "passive"))
    )
    (net (code "71") (name "unconnected-(U$6-Pad+)") (class "Default")
      (node (ref "U$6") (pin "+") (pinfunction "+_+") (pintype "bidirectional"))
    )
    (net (code "72") (name "unconnected-(U$6-Pad-)") (class "Default")
      (node (ref "U$6") (pin "-") (pinfunction "-_-") (pintype "bidirectional"))
    )
    (net (code "73") (name "unconnected-(U$7-+-Pad-)") (class "Default")
      (node (ref "U$7") (pin "-") (pinfunction "+_-") (pintype "bidirectional"))
    )
    (net (code "74") (name "unconnected-(U$7---Pad+)") (class "Default")
      (node (ref "U$7") (pin "+") (pinfunction "-_+") (pintype "bidirectional"))
    )
  )
)
